# RS232.net
KiCad netlist of a schematic drawn in Altium Designer
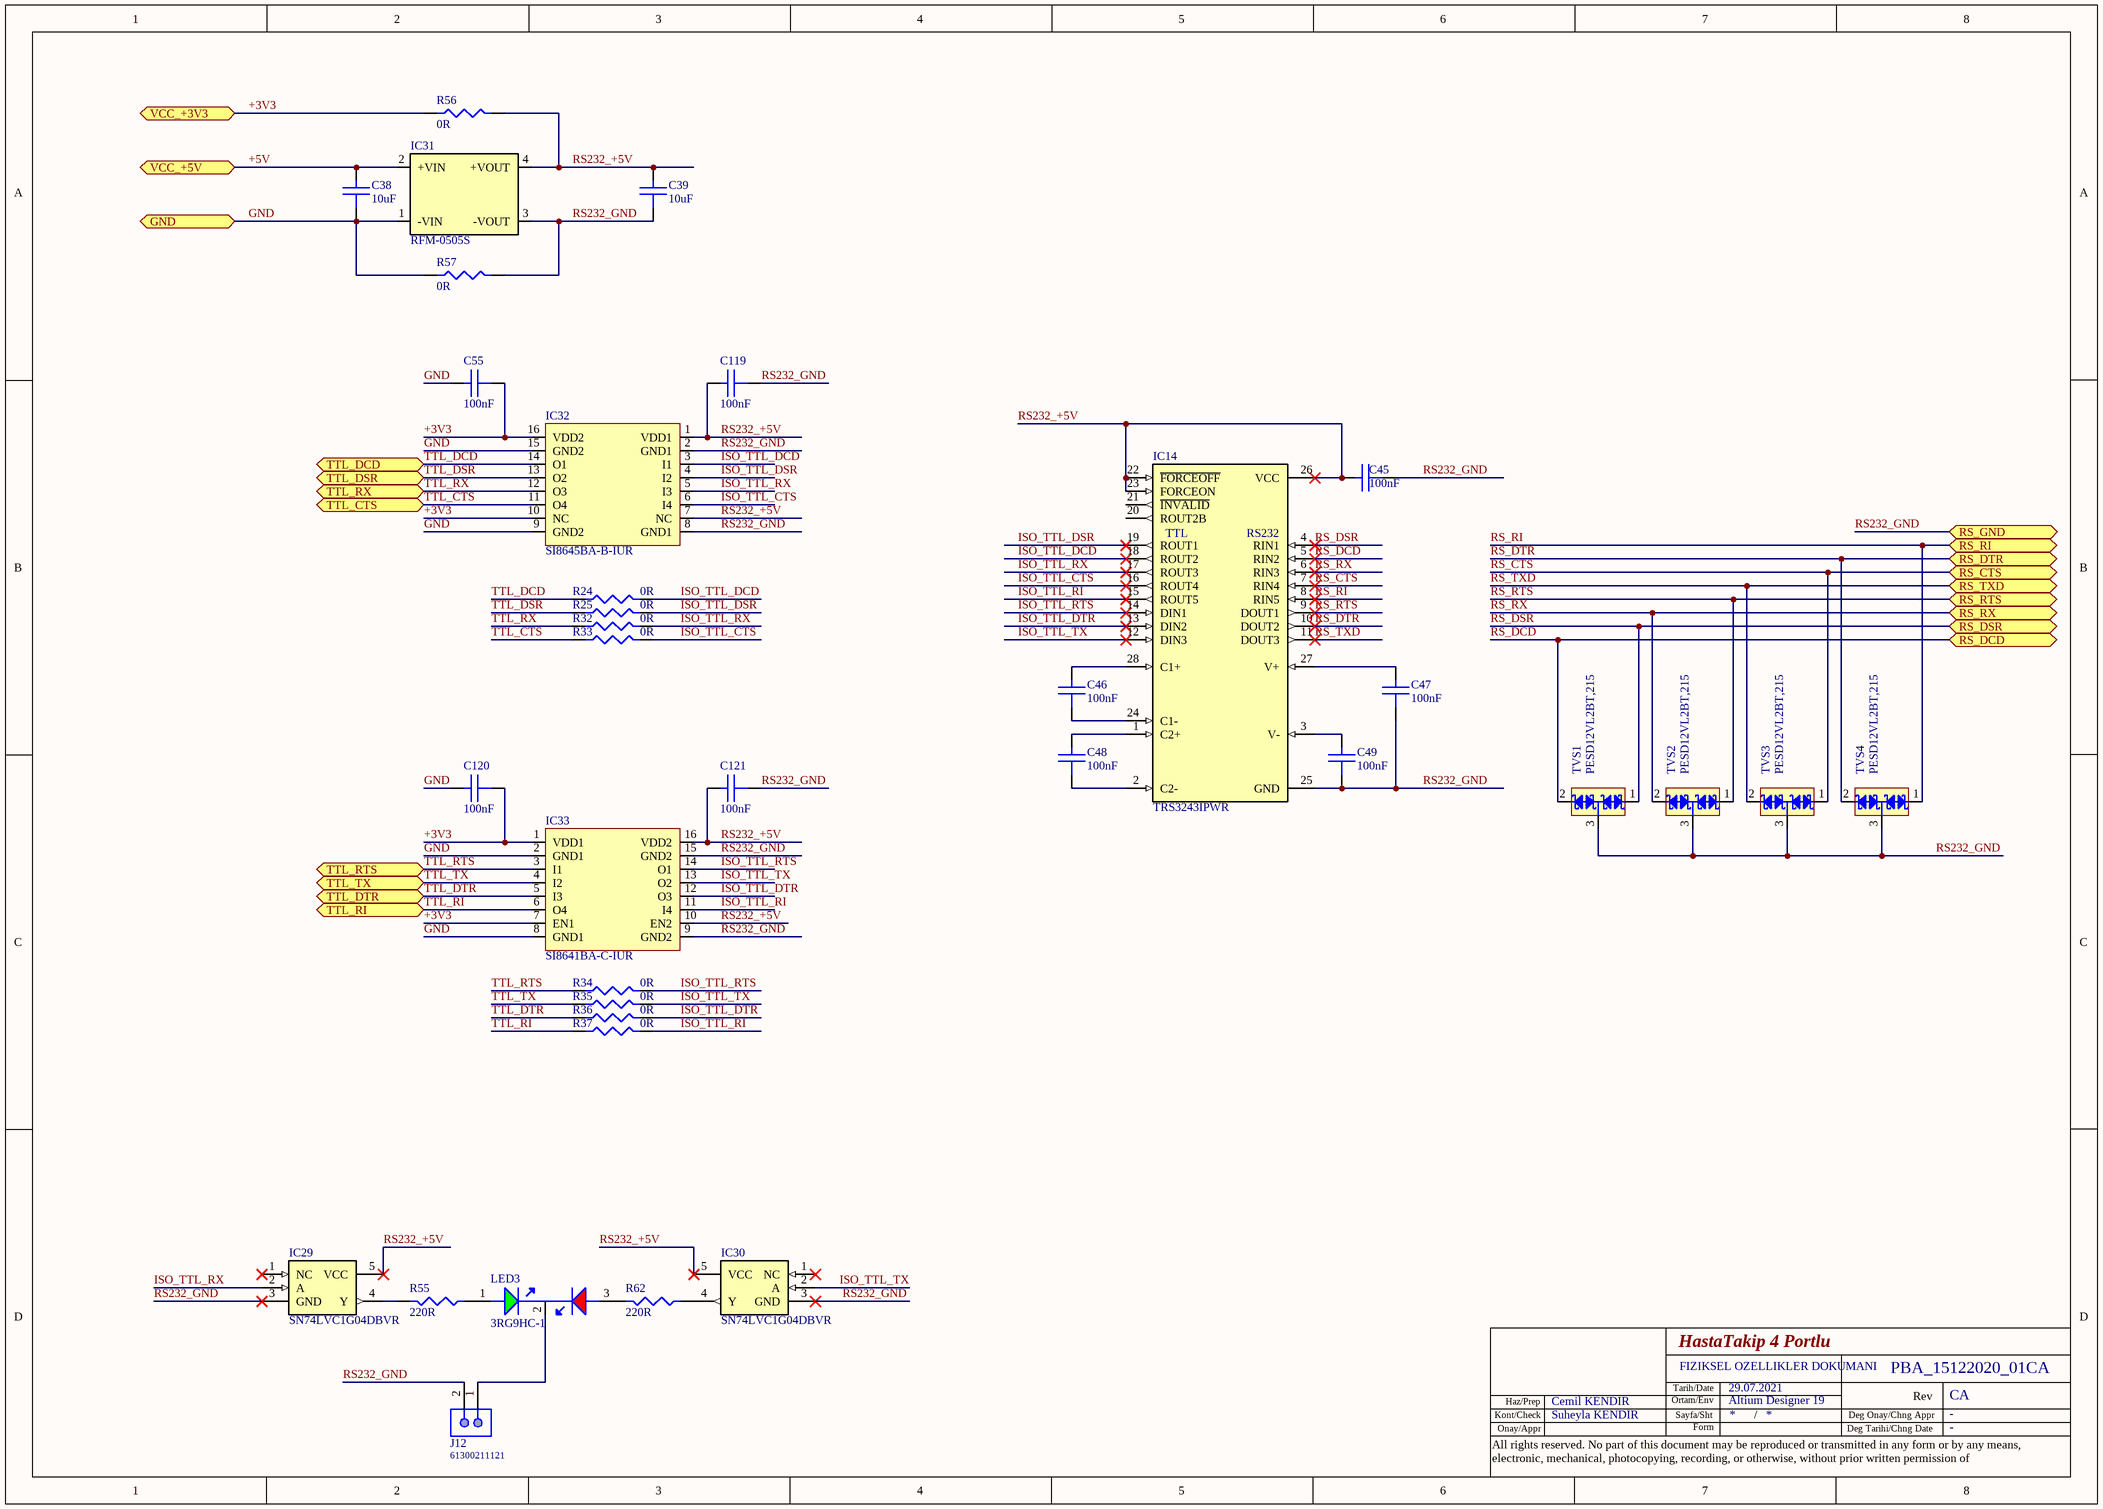
[diagram p0: RS232.SchDoc]

(export (version "E")
  (design (tool "Eeschema 10.0.6"))
  (components
    (comp (ref "C38")
      (value "10uF")
      (footprint "C0603")
      (description "10uF 10V X5R 20% SMD 0603 85C Paper T/R")
      (fields
        (field (name "MANUFACTURER") "Yageo")
        (field (name "MANUFACTURER PART NUMBER") "CC0603MRX5R6BB106")
      )
      (libsource (lib "McmLibrary") (part "CC0603MRX5R6BB106"))
    )
    (comp (ref "C39")
      (value "10uF")
      (footprint "C0603")
      (description "10uF 10V X5R 20% SMD 0603 85C Paper T/R")
      (fields
        (field (name "MANUFACTURER") "Yageo")
        (field (name "MANUFACTURER PART NUMBER") "CC0603MRX5R6BB106")
      )
      (libsource (lib "McmLibrary") (part "CC0603MRX5R6BB106"))
    )
    (comp (ref "C45")
      (value "100nF")
      (footprint "C0603")
      (description "100nF, 25V, X7R, 10%, 0603")
      (fields
        (field (name "MANUFACTURER") "Yageo")
        (field (name "MANUFACTURER PART NUMBER") "CC0603KRX7R8BB104")
      )
      (libsource (lib "McmLibrary") (part "CC0603KRX7R8BB104"))
    )
    (comp (ref "C46")
      (value "100nF")
      (footprint "C0603")
      (description "100nF, 25V, X7R, 10%, 0603")
      (fields
        (field (name "MANUFACTURER") "Yageo")
        (field (name "MANUFACTURER PART NUMBER") "CC0603KRX7R8BB104")
      )
      (libsource (lib "McmLibrary") (part "CC0603KRX7R8BB104"))
    )
    (comp (ref "C47")
      (value "100nF")
      (footprint "C0603")
      (description "100nF, 25V, X7R, 10%, 0603")
      (fields
        (field (name "MANUFACTURER") "Yageo")
        (field (name "MANUFACTURER PART NUMBER") "CC0603KRX7R8BB104")
      )
      (libsource (lib "McmLibrary") (part "CC0603KRX7R8BB104"))
    )
    (comp (ref "C48")
      (value "100nF")
      (footprint "C0603")
      (description "100nF, 25V, X7R, 10%, 0603")
      (fields
        (field (name "MANUFACTURER") "Yageo")
        (field (name "MANUFACTURER PART NUMBER") "CC0603KRX7R8BB104")
      )
      (libsource (lib "McmLibrary") (part "CC0603KRX7R8BB104"))
    )
    (comp (ref "C49")
      (value "100nF")
      (footprint "C0603")
      (description "100nF, 25V, X7R, 10%, 0603")
      (fields
        (field (name "MANUFACTURER") "Yageo")
        (field (name "MANUFACTURER PART NUMBER") "CC0603KRX7R8BB104")
      )
      (libsource (lib "McmLibrary") (part "CC0603KRX7R8BB104"))
    )
    (comp (ref "C55")
      (value "100nF")
      (footprint "C0603")
      (description "100nF, 25V, X7R, 10%, 0603")
      (fields
        (field (name "MANUFACTURER") "Yageo")
        (field (name "MANUFACTURER PART NUMBER") "CC0603KRX7R8BB104")
      )
      (libsource (lib "McmLibrary") (part "CC0603KRX7R8BB104"))
    )
    (comp (ref "C119")
      (value "100nF")
      (footprint "C0603")
      (description "100nF, 25V, X7R, 10%, 0603")
      (fields
        (field (name "MANUFACTURER") "Yageo")
        (field (name "MANUFACTURER PART NUMBER") "CC0603KRX7R8BB104")
      )
      (libsource (lib "McmLibrary") (part "CC0603KRX7R8BB104"))
    )
    (comp (ref "C120")
      (value "100nF")
      (footprint "C0603")
      (description "100nF, 25V, X7R, 10%, 0603")
      (fields
        (field (name "MANUFACTURER") "Yageo")
        (field (name "MANUFACTURER PART NUMBER") "CC0603KRX7R8BB104")
      )
      (libsource (lib "McmLibrary") (part "CC0603KRX7R8BB104"))
    )
    (comp (ref "C121")
      (value "100nF")
      (footprint "C0603")
      (description "100nF, 25V, X7R, 10%, 0603")
      (fields
        (field (name "MANUFACTURER") "Yageo")
        (field (name "MANUFACTURER PART NUMBER") "CC0603KRX7R8BB104")
      )
      (libsource (lib "McmLibrary") (part "CC0603KRX7R8BB104"))
    )
    (comp (ref "IC14")
      (value "TRS3243IPWR")
      (footprint "TSSOP-28")
      (fields (field (name "MANUFACTURER") "Texas Instruments"))
      (libsource (lib "InterfaceDriversReceiversTransceivers") (part "TRS3243IPWR"))
    )
    (comp (ref "IC29")
      (value "SN74LVC1G04DBVR")
      (footprint "SOT-23-5")
      (description "Inverter 1-Element CMOS 5-Pin SOT-23 T/R")
      (fields (field (name "MANUFACTURER") "Texas Instruments"))
      (libsource (lib "") (part "SN74LVC1G04DBVR_1"))
    )
    (comp (ref "IC30")
      (value "SN74LVC1G04DBVR")
      (footprint "SOT-23-5")
      (description "Inverter 1-Element CMOS 5-Pin SOT-23 T/R")
      (fields (field (name "MANUFACTURER") "Texas Instruments"))
      (libsource (lib "McmLibrary") (part "SN74LVC1G04DBVR"))
    )
    (comp (ref "IC31")
      (value "RFM-0505S")
      (footprint "RFM-0505S")
      (fields (field (name "MANUFACTURER") "Recom"))
      (libsource (lib "Module") (part "RFM-0505S"))
    )
    (comp (ref "IC32")
      (value "SI8645BA-B-IUR")
      (footprint "QSOP16")
      (description "Digital Isolator CMOS 4-CH 150Mbps Automotive 16-Pin QSOP T/R")
      (fields (field (name "MANUFACTURER") "Silicon Labs"))
      (libsource (lib "McmLibrary") (part "SI8645BA-B-IUR"))
    )
    (comp (ref "IC33")
      (value "SI8641BA-C-IUR")
      (footprint "QSOP16")
      (fields (field (name "MANUFACTURER") "Silicon Labs"))
      (libsource (lib "McmLibrary") (part "SI8641BA-C-IUR"))
    )
    (comp (ref "J12")
      (value "61300211121")
      (footprint "61300211121")
      (description "WR-PHD Pin Header, THT, pitch 2.54mm, Single Row, Vertical, 2pin")
      (fields (field (name "MANUFACTURER") "Wurth Electronics") (field (name "PUBLISHER") "Wurth Elektronik"))
      (libsource (lib "McmLibrary") (part "61300211121"))
    )
    (comp (ref "LED3")
      (value "3RG9HC-1")
      (footprint "3RG9HC-1")
      (description "LED 3MM RED, GREEN R:30mcd, G:60mcd 40°")
      (fields (field (name "MANUFACTURER") "STRONG BASE"))
      (libsource (lib "McmLibrary") (part "3RG9HC-1"))
    )
    (comp (ref "R24")
      (value "0R")
      (footprint "R0603")
      (description "0R ,%1 ,1/10 W ,0603")
      (fields
        (field (name "MANUFACTURER") "Yageo")
        (field (name "MANUFACTURER PART NUMBER") "RC0603FR-070RL")
      )
      (libsource (lib "McmLibrary") (part "RC0603FR-070RL"))
    )
    (comp (ref "R25")
      (value "0R")
      (footprint "R0603")
      (description "0R ,%1 ,1/10 W ,0603")
      (fields
        (field (name "MANUFACTURER") "Yageo")
        (field (name "MANUFACTURER PART NUMBER") "RC0603FR-070RL")
      )
      (libsource (lib "McmLibrary") (part "RC0603FR-070RL"))
    )
    (comp (ref "R32")
      (value "0R")
      (footprint "R0603")
      (description "0R ,%1 ,1/10 W ,0603")
      (fields
        (field (name "MANUFACTURER") "Yageo")
        (field (name "MANUFACTURER PART NUMBER") "RC0603FR-070RL")
      )
      (libsource (lib "McmLibrary") (part "RC0603FR-070RL"))
    )
    (comp (ref "R33")
      (value "0R")
      (footprint "R0603")
      (description "0R ,%1 ,1/10 W ,0603")
      (fields
        (field (name "MANUFACTURER") "Yageo")
        (field (name "MANUFACTURER PART NUMBER") "RC0603FR-070RL")
      )
      (libsource (lib "McmLibrary") (part "RC0603FR-070RL"))
    )
    (comp (ref "R34")
      (value "0R")
      (footprint "R0603")
      (description "0R ,%1 ,1/10 W ,0603")
      (fields
        (field (name "MANUFACTURER") "Yageo")
        (field (name "MANUFACTURER PART NUMBER") "RC0603FR-070RL")
      )
      (libsource (lib "McmLibrary") (part "RC0603FR-070RL"))
    )
    (comp (ref "R35")
      (value "0R")
      (footprint "R0603")
      (description "0R ,%1 ,1/10 W ,0603")
      (fields
        (field (name "MANUFACTURER") "Yageo")
        (field (name "MANUFACTURER PART NUMBER") "RC0603FR-070RL")
      )
      (libsource (lib "McmLibrary") (part "RC0603FR-070RL"))
    )
    (comp (ref "R36")
      (value "0R")
      (footprint "R0603")
      (description "0R ,%1 ,1/10 W ,0603")
      (fields
        (field (name "MANUFACTURER") "Yageo")
        (field (name "MANUFACTURER PART NUMBER") "RC0603FR-070RL")
      )
      (libsource (lib "McmLibrary") (part "RC0603FR-070RL"))
    )
    (comp (ref "R37")
      (value "0R")
      (footprint "R0603")
      (description "0R ,%1 ,1/10 W ,0603")
      (fields
        (field (name "MANUFACTURER") "Yageo")
        (field (name "MANUFACTURER PART NUMBER") "RC0603FR-070RL")
      )
      (libsource (lib "McmLibrary") (part "RC0603FR-070RL"))
    )
    (comp (ref "R55")
      (value "220R")
      (footprint "R0603")
      (description "220 R, %1, 1/10W, 0603")
      (fields
        (field (name "MANUFACTURER") "Yageo")
        (field (name "MANUFACTURER PART NUMBER") "RC0603FR-07220RL")
      )
      (libsource (lib "McmLibrary") (part "RC0603FR-07220RL"))
    )
    (comp (ref "R56")
      (value "0R")
      (footprint "R0603")
      (description "0R ,%1 ,1/10 W ,0603")
      (fields
        (field (name "MANUFACTURER") "Yageo")
        (field (name "MANUFACTURER PART NUMBER") "RC0603FR-070RL")
      )
      (libsource (lib "McmLibrary") (part "RC0603FR-070RL"))
    )
    (comp (ref "R57")
      (value "0R")
      (footprint "R0603")
      (description "0R ,%1 ,1/10 W ,0603")
      (fields
        (field (name "MANUFACTURER") "Yageo")
        (field (name "MANUFACTURER PART NUMBER") "RC0603FR-070RL")
      )
      (libsource (lib "McmLibrary") (part "RC0603FR-070RL"))
    )
    (comp (ref "R62")
      (value "220R")
      (footprint "R0603")
      (description "220 R, %1, 1/10W, 0603")
      (fields
        (field (name "MANUFACTURER") "Yageo")
        (field (name "MANUFACTURER PART NUMBER") "RC0603FR-07220RL")
      )
      (libsource (lib "McmLibrary") (part "RC0603FR-07220RL"))
    )
    (comp (ref "TVS1")
      (value "PESD12VL2BT,215")
      (footprint "SOT-23")
      (description "TVS DIODE 12V 37V SOT23")
      (fields (field (name "MANUFACTURER") "Nexperia"))
      (libsource (lib "McmLibrary") (part "PESD12VL2BT,215"))
    )
    (comp (ref "TVS2")
      (value "PESD12VL2BT,215")
      (footprint "SOT-23")
      (description "TVS DIODE 12V 37V SOT23")
      (fields (field (name "MANUFACTURER") "Nexperia"))
      (libsource (lib "McmLibrary") (part "PESD12VL2BT,215"))
    )
    (comp (ref "TVS3")
      (value "PESD12VL2BT,215")
      (footprint "SOT-23")
      (description "TVS DIODE 12V 37V SOT23")
      (fields (field (name "MANUFACTURER") "Nexperia"))
      (libsource (lib "McmLibrary") (part "PESD12VL2BT,215"))
    )
    (comp (ref "TVS4")
      (value "PESD12VL2BT,215")
      (footprint "SOT-23")
      (description "TVS DIODE 12V 37V SOT23")
      (fields (field (name "MANUFACTURER") "Nexperia"))
      (libsource (lib "McmLibrary") (part "PESD12VL2BT,215"))
    )
  )
  (nets
    (net (code "1") (name "/+3V3") (class "Default")
      (node (ref "C120") (pin "2") (pintype "passive"))
      (node (ref "C55") (pin "2") (pintype "passive"))
      (node (ref "IC32") (pin "10") (pinfunction "NC_10") (pintype "passive"))
      (node (ref "IC32") (pin "16") (pinfunction "VDD2_16") (pintype "passive"))
      (node (ref "IC33") (pin "1") (pinfunction "VDD1_1") (pintype "passive"))
      (node (ref "IC33") (pin "7") (pinfunction "EN1_7") (pintype "passive"))
      (node (ref "R56") (pin "1") (pinfunction "1_1") (pintype "passive"))
    )
    (net (code "2") (name "/+5V") (class "Default")
      (node (ref "C38") (pin "1") (pintype "passive"))
      (node (ref "IC31") (pin "2") (pinfunction "+VIN_2") (pintype "passive"))
    )
    (net (code "3") (name "/GND") (class "Default")
      (node (ref "C120") (pin "1") (pintype "passive"))
      (node (ref "C38") (pin "2") (pintype "passive"))
      (node (ref "C55") (pin "1") (pintype "passive"))
      (node (ref "IC31") (pin "1") (pinfunction "-VIN_1") (pintype "passive"))
      (node (ref "IC32") (pin "15") (pinfunction "GND2_15") (pintype "passive"))
      (node (ref "IC32") (pin "9") (pinfunction "GND2_9") (pintype "passive"))
      (node (ref "IC33") (pin "2") (pinfunction "GND1_2") (pintype "passive"))
      (node (ref "IC33") (pin "8") (pinfunction "GND1_8") (pintype "passive"))
      (node (ref "R57") (pin "1") (pinfunction "1_1") (pintype "passive"))
    )
    (net (code "4") (name "/ISO_TTL_CTS") (class "Default")
      (node (ref "IC14") (pin "16") (pinfunction "ROUT4_16") (pintype "output"))
      (node (ref "IC32") (pin "6") (pinfunction "I4_6") (pintype "passive"))
      (node (ref "R33") (pin "2") (pinfunction "2_2") (pintype "passive"))
    )
    (net (code "5") (name "/ISO_TTL_DCD") (class "Default")
      (node (ref "IC14") (pin "18") (pinfunction "ROUT2_18") (pintype "output"))
      (node (ref "IC32") (pin "3") (pinfunction "I1_3") (pintype "passive"))
      (node (ref "R24") (pin "2") (pinfunction "2_2") (pintype "passive"))
    )
    (net (code "6") (name "/ISO_TTL_DSR") (class "Default")
      (node (ref "IC14") (pin "19") (pinfunction "ROUT1_19") (pintype "output"))
      (node (ref "IC32") (pin "4") (pinfunction "I2_4") (pintype "passive"))
      (node (ref "R25") (pin "2") (pinfunction "2_2") (pintype "passive"))
    )
    (net (code "7") (name "/ISO_TTL_DTR") (class "Default")
      (node (ref "IC14") (pin "13") (pinfunction "DIN2_13") (pintype "input"))
      (node (ref "IC33") (pin "12") (pinfunction "O3_12") (pintype "passive"))
      (node (ref "R36") (pin "2") (pinfunction "2_2") (pintype "passive"))
    )
    (net (code "8") (name "/ISO_TTL_RI") (class "Default")
      (node (ref "IC14") (pin "15") (pinfunction "ROUT5_15") (pintype "output"))
      (node (ref "IC33") (pin "11") (pinfunction "I4_11") (pintype "passive"))
      (node (ref "R37") (pin "2") (pinfunction "2_2") (pintype "passive"))
    )
    (net (code "9") (name "/ISO_TTL_RTS") (class "Default")
      (node (ref "IC14") (pin "14") (pinfunction "DIN1_14") (pintype "input"))
      (node (ref "IC33") (pin "14") (pinfunction "O1_14") (pintype "passive"))
      (node (ref "R34") (pin "2") (pinfunction "2_2") (pintype "passive"))
    )
    (net (code "10") (name "/ISO_TTL_RX") (class "Default")
      (node (ref "IC14") (pin "17") (pinfunction "ROUT3_17") (pintype "output"))
      (node (ref "IC29") (pin "2") (pinfunction "A_2") (pintype "input"))
      (node (ref "IC32") (pin "5") (pinfunction "I3_5") (pintype "passive"))
      (node (ref "R32") (pin "2") (pinfunction "2_2") (pintype "passive"))
    )
    (net (code "11") (name "/ISO_TTL_TX") (class "Default")
      (node (ref "IC14") (pin "12") (pinfunction "DIN3_12") (pintype "input"))
      (node (ref "IC30") (pin "2") (pinfunction "A_2") (pintype "input"))
      (node (ref "IC33") (pin "13") (pinfunction "O2_13") (pintype "passive"))
      (node (ref "R35") (pin "2") (pinfunction "2_2") (pintype "passive"))
    )
    (net (code "12") (name "/RS232_+5V") (class "Default")
      (node (ref "C119") (pin "1") (pintype "passive"))
      (node (ref "C121") (pin "1") (pintype "passive"))
      (node (ref "C39") (pin "1") (pintype "passive"))
      (node (ref "C45") (pin "1") (pintype "passive"))
      (node (ref "IC14") (pin "22") (pinfunction "~{FORCEOFF}_22") (pintype "input"))
      (node (ref "IC14") (pin "23") (pinfunction "FORCEON_23") (pintype "input"))
      (node (ref "IC14") (pin "26") (pinfunction "VCC_26") (pintype "power_in"))
      (node (ref "IC29") (pin "5") (pinfunction "VCC_5") (pintype "power_in"))
      (node (ref "IC30") (pin "5") (pinfunction "VCC_5") (pintype "power_in"))
      (node (ref "IC31") (pin "4") (pinfunction "+VOUT_4") (pintype "passive"))
      (node (ref "IC32") (pin "1") (pinfunction "VDD1_1") (pintype "passive"))
      (node (ref "IC32") (pin "7") (pinfunction "NC_7") (pintype "passive"))
      (node (ref "IC33") (pin "10") (pinfunction "EN2_10") (pintype "passive"))
      (node (ref "IC33") (pin "16") (pinfunction "VDD2_16") (pintype "passive"))
      (node (ref "R56") (pin "2") (pinfunction "2_2") (pintype "passive"))
    )
    (net (code "13") (name "/RS232_GND") (class "Default")
      (node (ref "C119") (pin "2") (pintype "passive"))
      (node (ref "C121") (pin "2") (pintype "passive"))
      (node (ref "C39") (pin "2") (pintype "passive"))
      (node (ref "C45") (pin "2") (pintype "passive"))
      (node (ref "C47") (pin "2") (pintype "passive"))
      (node (ref "C49") (pin "2") (pintype "passive"))
      (node (ref "IC14") (pin "25") (pinfunction "GND_25") (pintype "power_in"))
      (node (ref "IC29") (pin "3") (pinfunction "GND_3") (pintype "power_in"))
      (node (ref "IC30") (pin "3") (pinfunction "GND_3") (pintype "power_in"))
      (node (ref "IC31") (pin "3") (pinfunction "-VOUT_3") (pintype "passive"))
      (node (ref "IC32") (pin "2") (pinfunction "GND1_2") (pintype "passive"))
      (node (ref "IC32") (pin "8") (pinfunction "GND1_8") (pintype "passive"))
      (node (ref "IC33") (pin "15") (pinfunction "GND2_15") (pintype "passive"))
      (node (ref "IC33") (pin "9") (pinfunction "GND2_9") (pintype "passive"))
      (node (ref "J12") (pin "2") (pinfunction "2_2") (pintype "passive"))
      (node (ref "R57") (pin "2") (pinfunction "2_2") (pintype "passive"))
      (node (ref "TVS1") (pin "3") (pinfunction "3_3") (pintype "passive"))
      (node (ref "TVS2") (pin "3") (pinfunction "3_3") (pintype "passive"))
      (node (ref "TVS3") (pin "3") (pinfunction "3_3") (pintype "passive"))
      (node (ref "TVS4") (pin "3") (pinfunction "3_3") (pintype "passive"))
    )
    (net (code "14") (name "/RS_CTS") (class "Default")
      (node (ref "IC14") (pin "7") (pinfunction "RIN4_7") (pintype "input"))
      (node (ref "TVS3") (pin "1") (pinfunction "1_1") (pintype "passive"))
    )
    (net (code "15") (name "/RS_DCD") (class "Default")
      (node (ref "IC14") (pin "5") (pinfunction "RIN2_5") (pintype "input"))
      (node (ref "TVS1") (pin "2") (pinfunction "2_2") (pintype "passive"))
    )
    (net (code "16") (name "/RS_DSR") (class "Default")
      (node (ref "IC14") (pin "4") (pinfunction "RIN1_4") (pintype "input"))
      (node (ref "TVS1") (pin "1") (pinfunction "1_1") (pintype "passive"))
    )
    (net (code "17") (name "/RS_DTR") (class "Default")
      (node (ref "IC14") (pin "10") (pinfunction "DOUT2_10") (pintype "output"))
      (node (ref "TVS4") (pin "2") (pinfunction "2_2") (pintype "passive"))
    )
    (net (code "18") (name "/RS_RI") (class "Default")
      (node (ref "IC14") (pin "8") (pinfunction "RIN5_8") (pintype "input"))
      (node (ref "TVS4") (pin "1") (pinfunction "1_1") (pintype "passive"))
    )
    (net (code "19") (name "/RS_RTS") (class "Default")
      (node (ref "IC14") (pin "9") (pinfunction "DOUT1_9") (pintype "output"))
      (node (ref "TVS2") (pin "1") (pinfunction "1_1") (pintype "passive"))
    )
    (net (code "20") (name "/RS_RX") (class "Default")
      (node (ref "IC14") (pin "6") (pinfunction "RIN3_6") (pintype "input"))
      (node (ref "TVS2") (pin "2") (pinfunction "2_2") (pintype "passive"))
    )
    (net (code "21") (name "/RS_TXD") (class "Default")
      (node (ref "IC14") (pin "11") (pinfunction "DOUT3_11") (pintype "output"))
      (node (ref "TVS3") (pin "2") (pinfunction "2_2") (pintype "passive"))
    )
    (net (code "22") (name "/TTL_CTS") (class "Default")
      (node (ref "IC32") (pin "11") (pinfunction "O4_11") (pintype "passive"))
      (node (ref "R33") (pin "1") (pinfunction "1_1") (pintype "passive"))
    )
    (net (code "23") (name "/TTL_DCD") (class "Default")
      (node (ref "IC32") (pin "14") (pinfunction "O1_14") (pintype "passive"))
      (node (ref "R24") (pin "1") (pinfunction "1_1") (pintype "passive"))
    )
    (net (code "24") (name "/TTL_DSR") (class "Default")
      (node (ref "IC32") (pin "13") (pinfunction "O2_13") (pintype "passive"))
      (node (ref "R25") (pin "1") (pinfunction "1_1") (pintype "passive"))
    )
    (net (code "25") (name "/TTL_DTR") (class "Default")
      (node (ref "IC33") (pin "5") (pinfunction "I3_5") (pintype "passive"))
      (node (ref "R36") (pin "1") (pinfunction "1_1") (pintype "passive"))
    )
    (net (code "26") (name "/TTL_RI") (class "Default")
      (node (ref "IC33") (pin "6") (pinfunction "O4_6") (pintype "passive"))
      (node (ref "R37") (pin "1") (pinfunction "1_1") (pintype "passive"))
    )
    (net (code "27") (name "/TTL_RTS") (class "Default")
      (node (ref "IC33") (pin "3") (pinfunction "I1_3") (pintype "passive"))
      (node (ref "R34") (pin "1") (pinfunction "1_1") (pintype "passive"))
    )
    (net (code "28") (name "/TTL_RX") (class "Default")
      (node (ref "IC32") (pin "12") (pinfunction "O3_12") (pintype "passive"))
      (node (ref "R32") (pin "1") (pinfunction "1_1") (pintype "passive"))
    )
    (net (code "29") (name "/TTL_TX") (class "Default")
      (node (ref "IC33") (pin "4") (pinfunction "I2_4") (pintype "passive"))
      (node (ref "R35") (pin "1") (pinfunction "1_1") (pintype "passive"))
    )
    (net (code "30") (name "Net-(IC14-C1+)") (class "Default")
      (node (ref "C46") (pin "1") (pintype "passive"))
      (node (ref "IC14") (pin "28") (pinfunction "C1+_28") (pintype "input"))
    )
    (net (code "31") (name "Net-(IC14-C1-)") (class "Default")
      (node (ref "C46") (pin "2") (pintype "passive"))
      (node (ref "IC14") (pin "24") (pinfunction "C1-_24") (pintype "input"))
    )
    (net (code "32") (name "Net-(IC14-C2+)") (class "Default")
      (node (ref "C48") (pin "1") (pintype "passive"))
      (node (ref "IC14") (pin "1") (pinfunction "C2+_1") (pintype "input"))
    )
    (net (code "33") (name "Net-(IC14-C2-)") (class "Default")
      (node (ref "C48") (pin "2") (pintype "passive"))
      (node (ref "IC14") (pin "2") (pinfunction "C2-_2") (pintype "input"))
    )
    (net (code "34") (name "Net-(IC14-V+)") (class "Default")
      (node (ref "C47") (pin "1") (pintype "passive"))
      (node (ref "IC14") (pin "27") (pinfunction "V+_27") (pintype "input"))
    )
    (net (code "35") (name "Net-(IC14-V-)") (class "Default")
      (node (ref "C49") (pin "1") (pintype "passive"))
      (node (ref "IC14") (pin "3") (pinfunction "V-_3") (pintype "input"))
    )
    (net (code "36") (name "Net-(IC29-Y)") (class "Default")
      (node (ref "IC29") (pin "4") (pinfunction "Y_4") (pintype "output"))
      (node (ref "R55") (pin "2") (pinfunction "2_2") (pintype "passive"))
    )
    (net (code "37") (name "Net-(IC30-Y)") (class "Default")
      (node (ref "IC30") (pin "4") (pinfunction "Y_4") (pintype "output"))
      (node (ref "R62") (pin "1") (pinfunction "1_1") (pintype "passive"))
    )
    (net (code "38") (name "Net-(J12-Pad1)") (class "Default")
      (node (ref "J12") (pin "1") (pinfunction "1_1") (pintype "passive"))
      (node (ref "LED3") (pin "2") (pinfunction "2_2") (pintype "passive"))
    )
    (net (code "39") (name "Net-(LED3-Pad1)") (class "Default")
      (node (ref "LED3") (pin "1") (pinfunction "1_1") (pintype "passive"))
      (node (ref "R55") (pin "1") (pinfunction "1_1") (pintype "passive"))
    )
    (net (code "40") (name "Net-(LED3-Pad3)") (class "Default")
      (node (ref "LED3") (pin "3") (pinfunction "3_3") (pintype "passive"))
      (node (ref "R62") (pin "2") (pinfunction "2_2") (pintype "passive"))
    )
    (net (code "41") (name "unconnected-(IC14-ROUT2B-Pad20)") (class "Default")
      (node (ref "IC14") (pin "20") (pinfunction "ROUT2B_20") (pintype "output"))
    )
    (net (code "42") (name "unconnected-(IC14-~{INVALID}-Pad21)") (class "Default")
      (node (ref "IC14") (pin "21") (pinfunction "~{INVALID}_21") (pintype "output"))
    )
    (net (code "43") (name "unconnected-(IC29-NC-Pad1)") (class "Default")
      (node (ref "IC29") (pin "1") (pinfunction "NC_1") (pintype "input+no_connect"))
    )
    (net (code "44") (name "unconnected-(IC30-NC-Pad1)") (class "Default")
      (node (ref "IC30") (pin "1") (pinfunction "NC_1") (pintype "input+no_connect"))
    )
  )
)
